# 09-RF_SUBG.net
KiCad netlist of a schematic drawn in Altium Designer
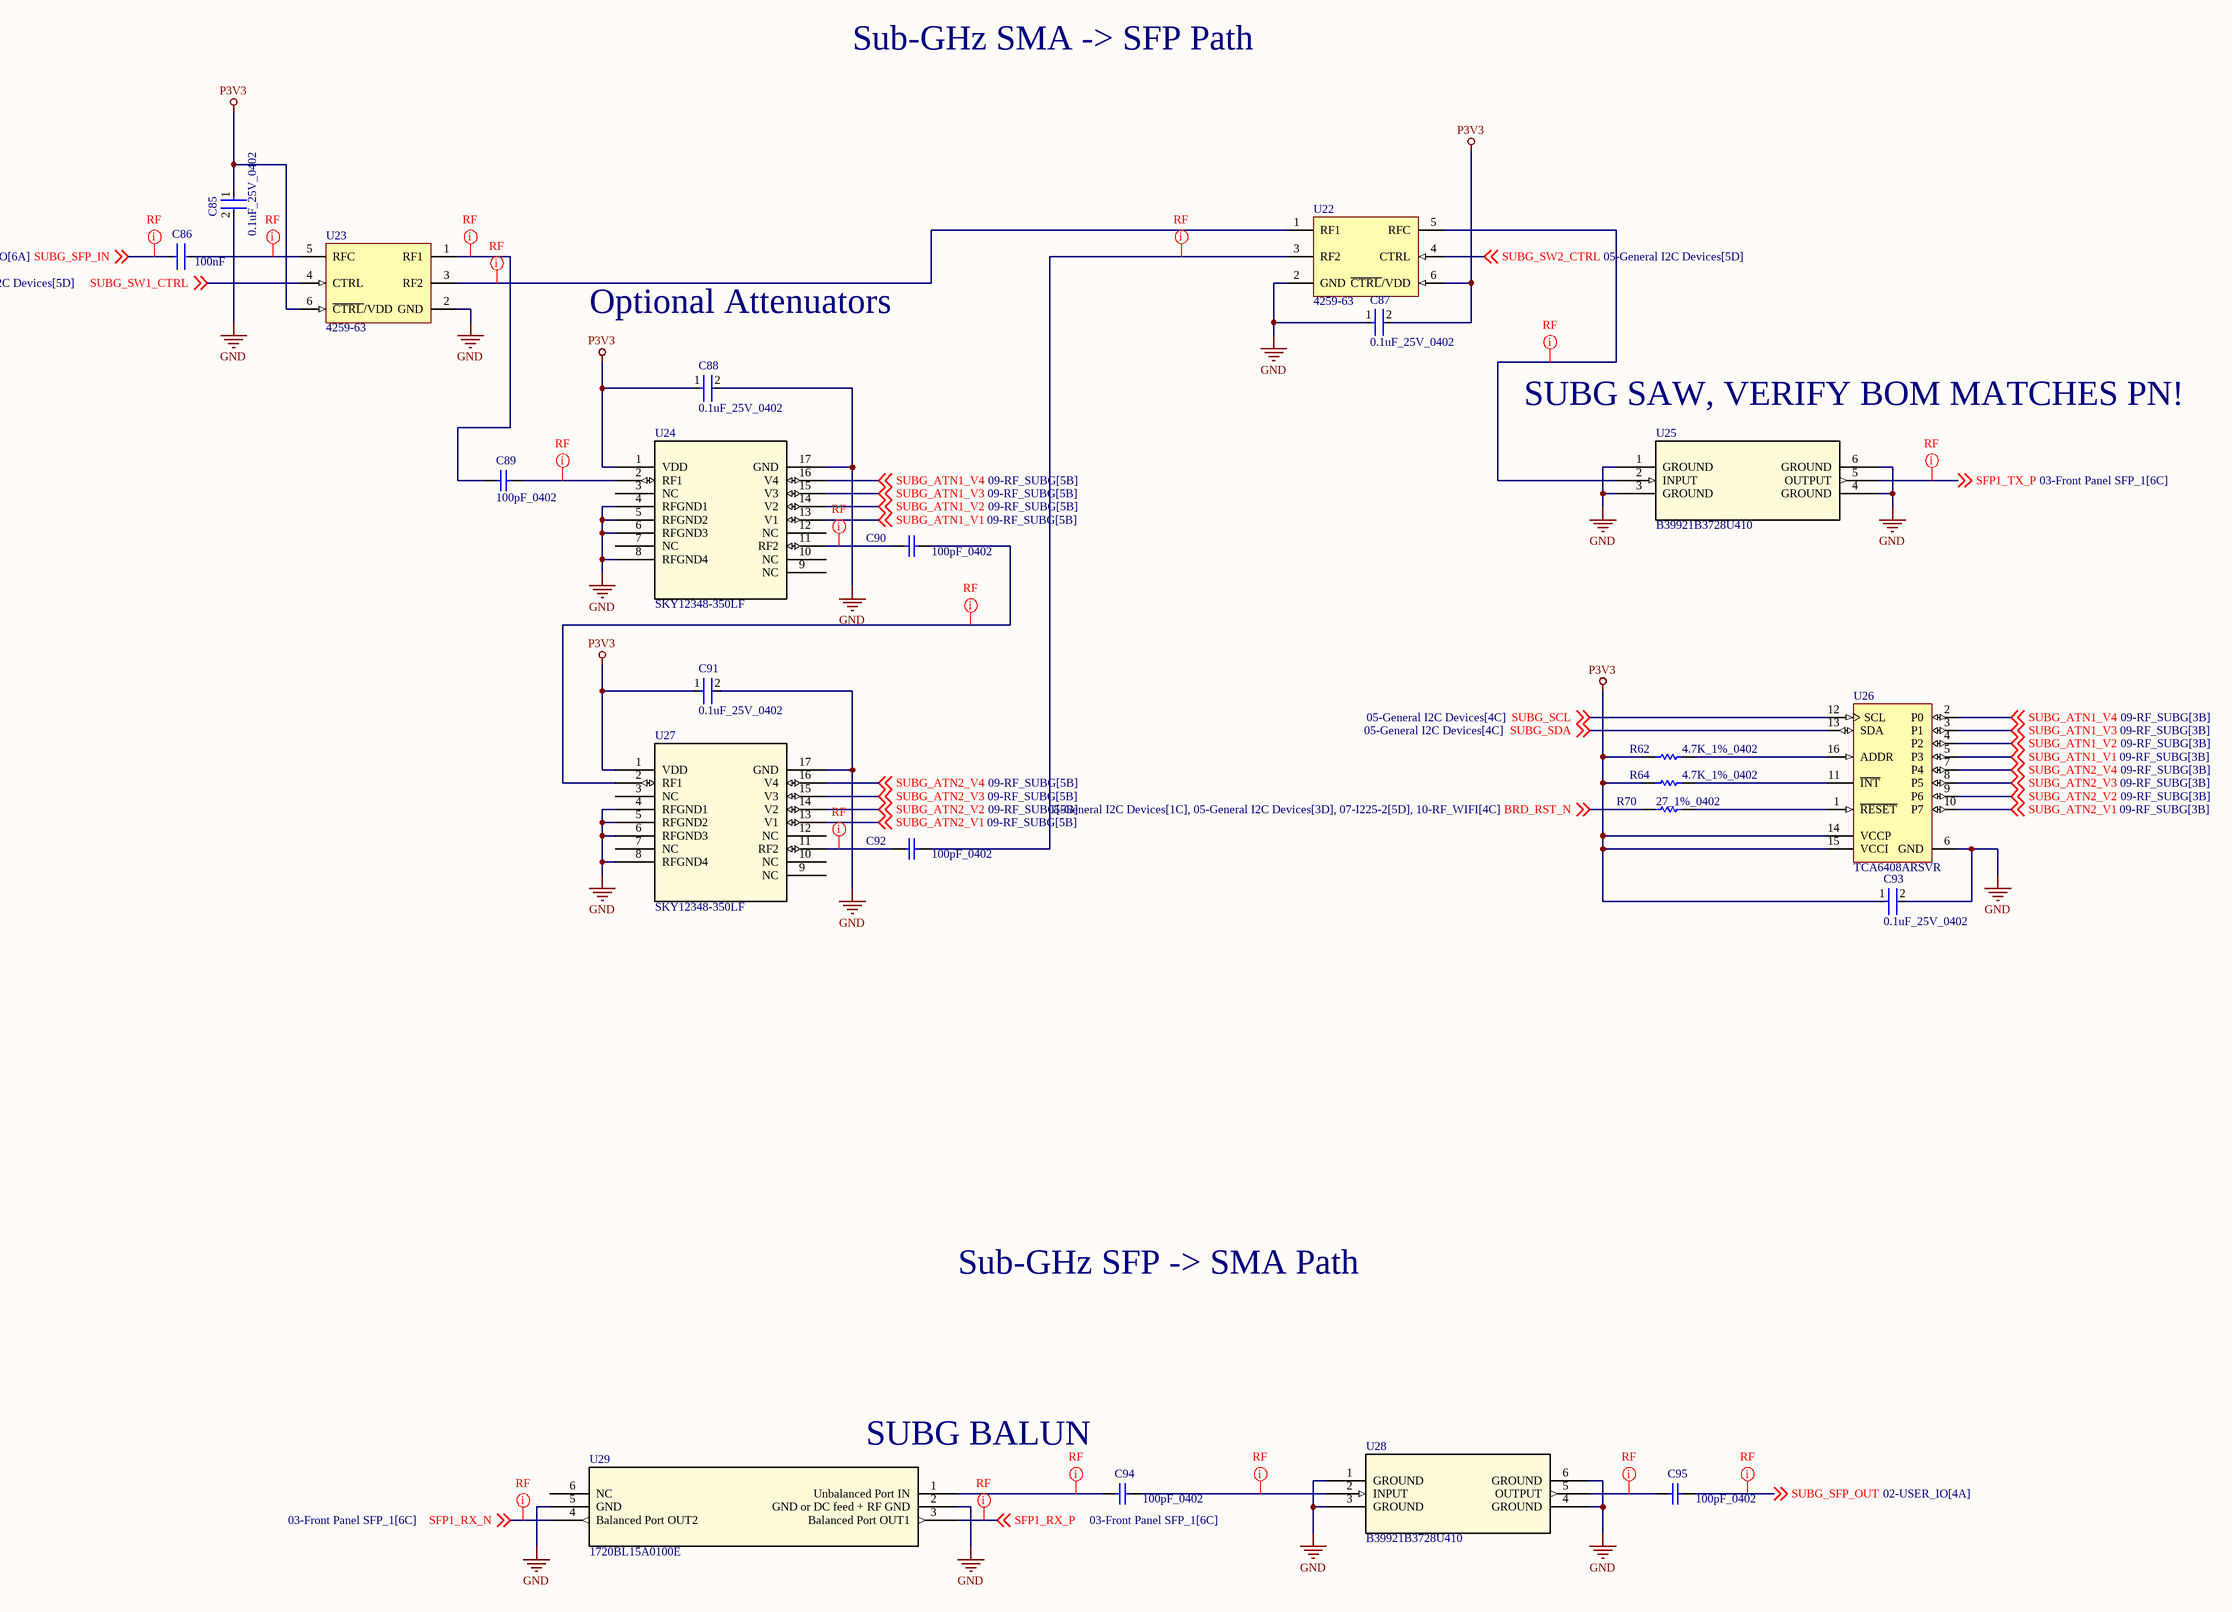
[diagram p0: 09-RF_SUBG.SchDoc]

(export (version "E")
  (design (tool "Eeschema 10.0.6"))
  (components
    (comp (ref "C85")
      (value "0.1uF_25V_0402")
      (footprint "FP-0402-L_1_0_1-W_0_5_0_1-IPC_C")
      (description "General Purpose Ceramic Capacitor, 0402, 100nF, 10%, X7R, 15%, 25V")
      (fields (field (name "VOLTAGE") "25V") (field (name "TOLERANCE") "10%"))
      (libsource (lib "Altium Content Vault") (part "b4654b650e69147ec39a6b967a45e02"))
    )
    (comp (ref "C86")
      (value "100nF")
      (footprint "FP-0402-L_1_0_0_05-W_0_5-IPC_B")
      (description "None")
      (fields (field (name "TOLERANCE") "10%"))
      (libsource (lib "") (part "b4654b650e69147ec39a6b967a45e02_1"))
    )
    (comp (ref "C87")
      (value "0.1uF_25V_0402")
      (footprint "FP-0402-L_1_0_1-W_0_5_0_1-IPC_C")
      (description "General Purpose Ceramic Capacitor, 0402, 100nF, 10%, X7R, 15%, 25V")
      (fields (field (name "VOLTAGE") "25V") (field (name "TOLERANCE") "10%"))
      (libsource (lib "Altium Content Vault") (part "b4654b650e69147ec39a6b967a45e02"))
    )
    (comp (ref "C88")
      (value "0.1uF_25V_0402")
      (footprint "FP-0402-L_1_0_1-W_0_5_0_1-IPC_C")
      (description "General Purpose Ceramic Capacitor, 0402, 100nF, 10%, X7R, 15%, 25V")
      (fields (field (name "VOLTAGE") "25V") (field (name "TOLERANCE") "10%"))
      (libsource (lib "Altium Content Vault") (part "b4654b650e69147ec39a6b967a45e02"))
    )
    (comp (ref "C89")
      (value "100pF_0402")
      (footprint "CAPC1005X55X25ML05T10")
      (fields (field (name "MANUFACTURER") "Murata") (field (name "PART NUMBER") "GRM1555C1H101JA01D"))
      (libsource (lib "Altium Content Vault") (part "CAP"))
    )
    (comp (ref "C90")
      (value "100pF_0402")
      (footprint "CAPC1005X55X25ML05T10")
      (fields (field (name "MANUFACTURER") "Murata") (field (name "PART NUMBER") "GRM1555C1H101JA01D"))
      (libsource (lib "Altium Content Vault") (part "CAP"))
    )
    (comp (ref "C91")
      (value "0.1uF_25V_0402")
      (footprint "FP-0402-L_1_0_1-W_0_5_0_1-IPC_C")
      (description "General Purpose Ceramic Capacitor, 0402, 100nF, 10%, X7R, 15%, 25V")
      (fields (field (name "VOLTAGE") "25V") (field (name "TOLERANCE") "10%"))
      (libsource (lib "Altium Content Vault") (part "b4654b650e69147ec39a6b967a45e02"))
    )
    (comp (ref "C92")
      (value "100pF_0402")
      (footprint "CAPC1005X55X25ML05T10")
      (fields (field (name "MANUFACTURER") "Murata") (field (name "PART NUMBER") "GRM1555C1H101JA01D"))
      (libsource (lib "Altium Content Vault") (part "CAP"))
    )
    (comp (ref "C93")
      (value "0.1uF_25V_0402")
      (footprint "FP-0402-L_1_0_1-W_0_5_0_1-IPC_C")
      (description "General Purpose Ceramic Capacitor, 0402, 100nF, 10%, X7R, 15%, 25V")
      (fields (field (name "VOLTAGE") "25V") (field (name "TOLERANCE") "10%"))
      (libsource (lib "Altium Content Vault") (part "b4654b650e69147ec39a6b967a45e02"))
    )
    (comp (ref "C94")
      (value "100pF_0402")
      (footprint "CAPC1005X55X25ML05T10")
      (fields (field (name "MANUFACTURER") "Murata") (field (name "PART NUMBER") "GRM1555C1H101JA01D"))
      (libsource (lib "Altium Content Vault") (part "CAP"))
    )
    (comp (ref "C95")
      (value "100pF_0402")
      (footprint "CAPC1005X55X25ML05T10")
      (fields (field (name "MANUFACTURER") "Murata") (field (name "PART NUMBER") "GRM1555C1H101JA01D"))
      (libsource (lib "Altium Content Vault") (part "CAP"))
    )
    (comp (ref "R62")
      (value "4.7K_1%_0402")
      (footprint "RESC1005X40X25NL10T10")
      (fields (field (name "MANUFACTURER") "Bourns") (field (name "PART NUMBER") "CR0402-FX-4701GLF"))
      (libsource (lib "Altium Content Vault") (part "RES"))
    )
    (comp (ref "R64")
      (value "4.7K_1%_0402")
      (footprint "RESC1005X40X25NL10T10")
      (fields (field (name "MANUFACTURER") "Bourns") (field (name "PART NUMBER") "CR0402-FX-4701GLF"))
      (libsource (lib "Altium Content Vault") (part "RES"))
    )
    (comp (ref "R70")
      (value "27_1%_0402")
      (footprint "RESC1005X40X25NL05T05")
      (fields (field (name "PART NUMBER") "CRCW040227R0FKED") (field (name "MANUFACTURER") "Vishay Dale"))
      (libsource (lib "Altium Content Vault") (part "RES"))
    )
    (comp (ref "U22")
      (value "4259-63")
      (footprint "PERE-SC-70-6_M")
      (description "IC RF Switch SPDT, 50 Ohm, 6-Pin SC70, RoHS, Tape and Reel")
      (fields (field (name "MANUFACTURER") "Peregrine Semiconductor"))
      (libsource (lib "") (part "PERE-PE4259-6_1"))
    )
    (comp (ref "U23")
      (value "4259-63")
      (footprint "PERE-SC-70-6_M")
      (description "IC RF Switch SPDT, 50 Ohm, 6-Pin SC70, RoHS, Tape and Reel")
      (fields (field (name "MANUFACTURER") "Peregrine Semiconductor"))
      (libsource (lib "Altium Content Vault") (part "PERE-PE4259-6"))
    )
    (comp (ref "U24")
      (value "SKY12348-350LF")
      (footprint "SKY12348-350LF_SKY")
      (description "No Description Available")
      (libsource (lib "SKY12348-350LF") (part "SKY12348-350LF"))
    )
    (comp (ref "U25")
      (value "B39921B3728U410")
      (footprint "B39162B3913U410_QUA")
      (description "No Description Available")
      (libsource (lib "B39162B3913U410") (part "B39162B3913U410"))
    )
    (comp (ref "U26")
      (value "TCA6408ARSVR")
      (footprint "RSV0016A_V")
      (fields (field (name "MANUFACTURER") "Texas Instruments"))
      (libsource (lib "Altium Content Vault") (part "TI-TCA6408A-UQFN_RSV-16"))
    )
    (comp (ref "U27")
      (value "SKY12348-350LF")
      (footprint "SKY12348-350LF_SKY")
      (description "No Description Available")
      (libsource (lib "SKY12348-350LF") (part "SKY12348-350LF"))
    )
    (comp (ref "U28")
      (value "B39921B3728U410")
      (footprint "B39162B3913U410_QUA")
      (description "No Description Available")
      (libsource (lib "B39162B3913U410") (part "B39162B3913U410"))
    )
    (comp (ref "U29")
      (value "1720BL15A0100E")
      (footprint "SMT_15B0050E_JOT")
      (description "No Description Available")
      (libsource (lib "1720BL15A0100E") (part "1720BL15A0100E"))
    )
  )
  (nets
    (net (code "1") (name "BRD_RST_N") (class "Default")
      (node (ref "R70") (pin "1") (pinfunction "1_1") (pintype "passive"))
    )
    (net (code "2") (name "GND") (class "Default")
      (node (ref "C85") (pin "2") (pinfunction "2_2") (pintype "passive"))
      (node (ref "C87") (pin "1") (pinfunction "1_1") (pintype "passive"))
      (node (ref "C88") (pin "2") (pinfunction "2_2") (pintype "passive"))
      (node (ref "C91") (pin "2") (pinfunction "2_2") (pintype "passive"))
      (node (ref "C93") (pin "2") (pinfunction "2_2") (pintype "passive"))
      (node (ref "U22") (pin "2") (pinfunction "GND_2") (pintype "power_in"))
      (node (ref "U23") (pin "2") (pinfunction "GND_2") (pintype "power_in"))
      (node (ref "U24") (pin "17") (pinfunction "GND_17") (pintype "power_in"))
      (node (ref "U24") (pin "4") (pinfunction "RFGND1_4") (pintype "power_in"))
      (node (ref "U24") (pin "5") (pinfunction "RFGND2_5") (pintype "power_in"))
      (node (ref "U24") (pin "6") (pinfunction "RFGND3_6") (pintype "power_in"))
      (node (ref "U24") (pin "8") (pinfunction "RFGND4_8") (pintype "power_in"))
      (node (ref "U25") (pin "1") (pinfunction "GROUND_1") (pintype "power_in"))
      (node (ref "U25") (pin "3") (pinfunction "GROUND_3") (pintype "power_in"))
      (node (ref "U25") (pin "4") (pinfunction "GROUND_4") (pintype "power_in"))
      (node (ref "U25") (pin "6") (pinfunction "GROUND_6") (pintype "power_in"))
      (node (ref "U26") (pin "6") (pinfunction "GND_6") (pintype "power_in"))
      (node (ref "U27") (pin "17") (pinfunction "GND_17") (pintype "power_in"))
      (node (ref "U27") (pin "4") (pinfunction "RFGND1_4") (pintype "power_in"))
      (node (ref "U27") (pin "5") (pinfunction "RFGND2_5") (pintype "power_in"))
      (node (ref "U27") (pin "6") (pinfunction "RFGND3_6") (pintype "power_in"))
      (node (ref "U27") (pin "8") (pinfunction "RFGND4_8") (pintype "power_in"))
      (node (ref "U28") (pin "1") (pinfunction "GROUND_1") (pintype "power_in"))
      (node (ref "U28") (pin "3") (pinfunction "GROUND_3") (pintype "power_in"))
      (node (ref "U28") (pin "4") (pinfunction "GROUND_4") (pintype "power_in"))
      (node (ref "U28") (pin "6") (pinfunction "GROUND_6") (pintype "power_in"))
      (node (ref "U29") (pin "2") (pinfunction "GND_or_DC_feed_+_RF_GND_2") (pintype "power_in"))
      (node (ref "U29") (pin "5") (pinfunction "GND_5") (pintype "power_in"))
    )
    (net (code "3") (name "Net-(U22-RF1)") (class "Default")
      (node (ref "U22") (pin "1") (pinfunction "RF1_1") (pintype "passive"))
      (node (ref "U23") (pin "3") (pinfunction "RF2_3") (pintype "passive"))
    )
    (net (code "4") (name "Net-(U22-RF2)") (class "Default")
      (node (ref "C92") (pin "2") (pinfunction "2_2") (pintype "passive"))
      (node (ref "U22") (pin "3") (pinfunction "RF2_3") (pintype "passive"))
    )
    (net (code "5") (name "Net-(U22-RFC)") (class "Default")
      (node (ref "U22") (pin "5") (pinfunction "RFC_5") (pintype "passive"))
      (node (ref "U25") (pin "2") (pinfunction "INPUT_2") (pintype "input"))
    )
    (net (code "6") (name "Net-(U23-RF1)") (class "Default")
      (node (ref "C89") (pin "1") (pinfunction "1_1") (pintype "passive"))
      (node (ref "U23") (pin "1") (pinfunction "RF1_1") (pintype "passive"))
    )
    (net (code "7") (name "Net-(U23-RFC)") (class "Default")
      (node (ref "C86") (pin "2") (pinfunction "2_2") (pintype "passive"))
      (node (ref "U23") (pin "5") (pinfunction "RFC_5") (pintype "passive"))
    )
    (net (code "8") (name "Net-(U24-RF1)") (class "Default")
      (node (ref "C89") (pin "2") (pinfunction "2_2") (pintype "passive"))
      (node (ref "U24") (pin "2") (pinfunction "RF1_2") (pintype "bidirectional"))
    )
    (net (code "9") (name "Net-(U24-RF2)") (class "Default")
      (node (ref "C90") (pin "1") (pinfunction "1_1") (pintype "passive"))
      (node (ref "U24") (pin "11") (pinfunction "RF2_11") (pintype "bidirectional"))
    )
    (net (code "10") (name "Net-(U26-ADDR)") (class "Default")
      (node (ref "R62") (pin "1") (pinfunction "1_1") (pintype "passive"))
      (node (ref "U26") (pin "16") (pinfunction "ADDR_16") (pintype "input"))
    )
    (net (code "11") (name "Net-(U26-~{INT})") (class "Default")
      (node (ref "R64") (pin "1") (pinfunction "1_1") (pintype "passive"))
      (node (ref "U26") (pin "11") (pinfunction "~{INT}_11") (pintype "open_collector"))
    )
    (net (code "12") (name "Net-(U26-~{RESET})") (class "Default")
      (node (ref "R70") (pin "2") (pinfunction "2_2") (pintype "passive"))
      (node (ref "U26") (pin "1") (pinfunction "~{RESET}_1") (pintype "input"))
    )
    (net (code "13") (name "Net-(U27-RF1)") (class "Default")
      (node (ref "C90") (pin "2") (pinfunction "2_2") (pintype "passive"))
      (node (ref "U27") (pin "2") (pinfunction "RF1_2") (pintype "bidirectional"))
    )
    (net (code "14") (name "Net-(U27-RF2)") (class "Default")
      (node (ref "C92") (pin "1") (pinfunction "1_1") (pintype "passive"))
      (node (ref "U27") (pin "11") (pinfunction "RF2_11") (pintype "bidirectional"))
    )
    (net (code "15") (name "Net-(U28-INPUT)") (class "Default")
      (node (ref "C94") (pin "2") (pinfunction "2_2") (pintype "passive"))
      (node (ref "U28") (pin "2") (pinfunction "INPUT_2") (pintype "input"))
    )
    (net (code "16") (name "Net-(U28-OUTPUT)") (class "Default")
      (node (ref "C95") (pin "1") (pinfunction "1_1") (pintype "passive"))
      (node (ref "U28") (pin "5") (pinfunction "OUTPUT_5") (pintype "output"))
    )
    (net (code "17") (name "Net-(U29-Unbalanced_Port_IN)") (class "Default")
      (node (ref "C94") (pin "1") (pinfunction "1_1") (pintype "passive"))
      (node (ref "U29") (pin "1") (pinfunction "Unbalanced_Port_IN_1") (pintype "passive"))
    )
    (net (code "18") (name "P3V3") (class "Default")
      (node (ref "C85") (pin "1") (pinfunction "1_1") (pintype "passive"))
      (node (ref "C87") (pin "2") (pinfunction "2_2") (pintype "passive"))
      (node (ref "C88") (pin "1") (pinfunction "1_1") (pintype "passive"))
      (node (ref "C91") (pin "1") (pinfunction "1_1") (pintype "passive"))
      (node (ref "C93") (pin "1") (pinfunction "1_1") (pintype "passive"))
      (node (ref "R62") (pin "2") (pinfunction "2_2") (pintype "passive"))
      (node (ref "R64") (pin "2") (pinfunction "2_2") (pintype "passive"))
      (node (ref "U22") (pin "6") (pinfunction "~{CTRL}/VDD_6") (pintype "input"))
      (node (ref "U23") (pin "6") (pinfunction "~{CTRL}/VDD_6") (pintype "input"))
      (node (ref "U24") (pin "1") (pinfunction "VDD_1") (pintype "power_in"))
      (node (ref "U26") (pin "14") (pinfunction "VCCP_14") (pintype "power_in"))
      (node (ref "U26") (pin "15") (pinfunction "VCCI_15") (pintype "power_in"))
      (node (ref "U27") (pin "1") (pinfunction "VDD_1") (pintype "power_in"))
    )
    (net (code "19") (name "SFP1_RX_N") (class "Default")
      (node (ref "U29") (pin "4") (pinfunction "Balanced_Port_OUT2_4") (pintype "output"))
    )
    (net (code "20") (name "SFP1_RX_P") (class "Default")
      (node (ref "U29") (pin "3") (pinfunction "Balanced_Port_OUT1_3") (pintype "output"))
    )
    (net (code "21") (name "SFP1_TX_P") (class "Default")
      (node (ref "U25") (pin "5") (pinfunction "OUTPUT_5") (pintype "output"))
    )
    (net (code "22") (name "SUBG_ATN1_V1") (class "Default")
      (node (ref "U24") (pin "13") (pinfunction "V1_13") (pintype "bidirectional"))
      (node (ref "U26") (pin "5") (pinfunction "P3_5") (pintype "bidirectional"))
    )
    (net (code "23") (name "SUBG_ATN1_V2") (class "Default")
      (node (ref "U24") (pin "14") (pinfunction "V2_14") (pintype "bidirectional"))
      (node (ref "U26") (pin "4") (pinfunction "P2_4") (pintype "bidirectional"))
    )
    (net (code "24") (name "SUBG_ATN1_V3") (class "Default")
      (node (ref "U24") (pin "15") (pinfunction "V3_15") (pintype "bidirectional"))
      (node (ref "U26") (pin "3") (pinfunction "P1_3") (pintype "bidirectional"))
    )
    (net (code "25") (name "SUBG_ATN1_V4") (class "Default")
      (node (ref "U24") (pin "16") (pinfunction "V4_16") (pintype "bidirectional"))
      (node (ref "U26") (pin "2") (pinfunction "P0_2") (pintype "bidirectional"))
    )
    (net (code "26") (name "SUBG_ATN2_V1") (class "Default")
      (node (ref "U26") (pin "10") (pinfunction "P7_10") (pintype "bidirectional"))
      (node (ref "U27") (pin "13") (pinfunction "V1_13") (pintype "bidirectional"))
    )
    (net (code "27") (name "SUBG_ATN2_V2") (class "Default")
      (node (ref "U26") (pin "9") (pinfunction "P6_9") (pintype "bidirectional"))
      (node (ref "U27") (pin "14") (pinfunction "V2_14") (pintype "bidirectional"))
    )
    (net (code "28") (name "SUBG_ATN2_V3") (class "Default")
      (node (ref "U26") (pin "8") (pinfunction "P5_8") (pintype "bidirectional"))
      (node (ref "U27") (pin "15") (pinfunction "V3_15") (pintype "bidirectional"))
    )
    (net (code "29") (name "SUBG_ATN2_V4") (class "Default")
      (node (ref "U26") (pin "7") (pinfunction "P4_7") (pintype "bidirectional"))
      (node (ref "U27") (pin "16") (pinfunction "V4_16") (pintype "bidirectional"))
    )
    (net (code "30") (name "SUBG_SCL") (class "Default")
      (node (ref "U26") (pin "12") (pinfunction "SCL_12") (pintype "input"))
    )
    (net (code "31") (name "SUBG_SDA") (class "Default")
      (node (ref "U26") (pin "13") (pinfunction "SDA_13") (pintype "bidirectional"))
    )
    (net (code "32") (name "SUBG_SFP_IN") (class "Default")
      (node (ref "C86") (pin "1") (pinfunction "1_1") (pintype "passive"))
    )
    (net (code "33") (name "SUBG_SFP_OUT") (class "Default")
      (node (ref "C95") (pin "2") (pinfunction "2_2") (pintype "passive"))
    )
    (net (code "34") (name "SUBG_SW1_CTRL") (class "Default")
      (node (ref "U23") (pin "4") (pinfunction "CTRL_4") (pintype "input"))
    )
    (net (code "35") (name "SUBG_SW2_CTRL") (class "Default")
      (node (ref "U22") (pin "4") (pinfunction "CTRL_4") (pintype "input"))
    )
    (net (code "36") (name "unconnected-(U24-NC-Pad3)") (class "Default")
      (node (ref "U24") (pin "3") (pinfunction "NC_3") (pintype "passive"))
    )
    (net (code "37") (name "unconnected-(U24-NC-Pad7)") (class "Default")
      (node (ref "U24") (pin "7") (pinfunction "NC_7") (pintype "passive"))
    )
    (net (code "38") (name "unconnected-(U24-NC-Pad9)") (class "Default")
      (node (ref "U24") (pin "9") (pinfunction "NC_9") (pintype "passive"))
    )
    (net (code "39") (name "unconnected-(U24-NC-Pad10)") (class "Default")
      (node (ref "U24") (pin "10") (pinfunction "NC_10") (pintype "passive"))
    )
    (net (code "40") (name "unconnected-(U24-NC-Pad12)") (class "Default")
      (node (ref "U24") (pin "12") (pinfunction "NC_12") (pintype "passive"))
    )
    (net (code "41") (name "unconnected-(U27-NC-Pad3)") (class "Default")
      (node (ref "U27") (pin "3") (pinfunction "NC_3") (pintype "passive"))
    )
    (net (code "42") (name "unconnected-(U27-NC-Pad7)") (class "Default")
      (node (ref "U27") (pin "7") (pinfunction "NC_7") (pintype "passive"))
    )
    (net (code "43") (name "unconnected-(U27-NC-Pad9)") (class "Default")
      (node (ref "U27") (pin "9") (pinfunction "NC_9") (pintype "passive"))
    )
    (net (code "44") (name "unconnected-(U27-NC-Pad10)") (class "Default")
      (node (ref "U27") (pin "10") (pinfunction "NC_10") (pintype "passive"))
    )
    (net (code "45") (name "unconnected-(U27-NC-Pad12)") (class "Default")
      (node (ref "U27") (pin "12") (pinfunction "NC_12") (pintype "passive"))
    )
    (net (code "46") (name "unconnected-(U29-NC-Pad6)") (class "Default")
      (node (ref "U29") (pin "6") (pinfunction "NC_6") (pintype "passive"))
    )
  )
)
